# PowerNest.net
KiCad netlist of a schematic drawn in EAGLE
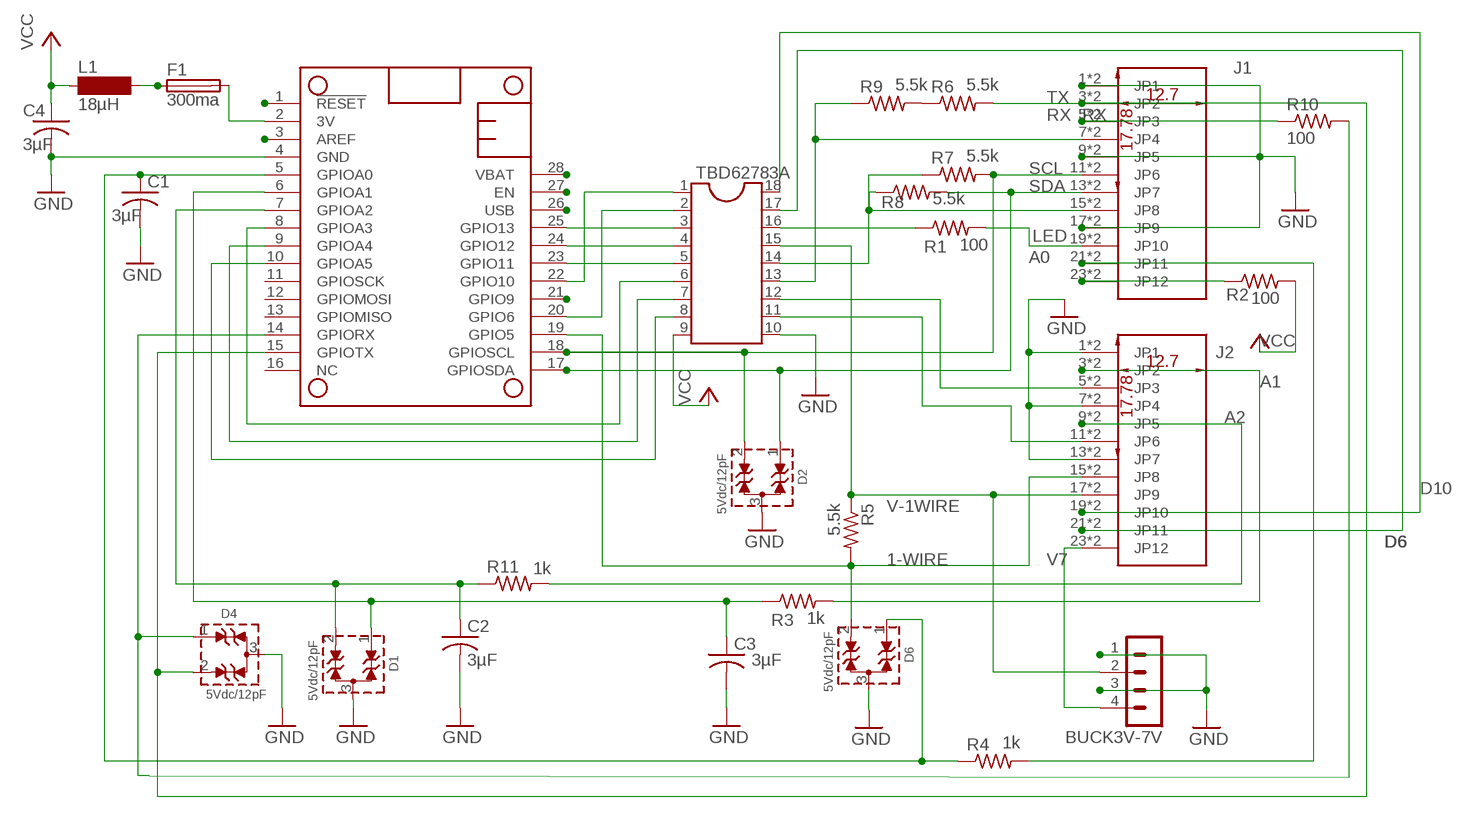
[diagram p0: schematic, sheet 1]

(export (version "E")
  (design (tool "Eeschema 10.0.6"))
  (components
    (comp (ref "BUCK3V-7V")
      (value "MA04-1")
      (footprint "eagle-import:MA04-1")
      (libsource (lib "eagle-import") (part "MA04-1"))
    )
    (comp (ref "C1")
      (value "3µF")
      (footprint "eagle-import:C1206K")
      (libsource (lib "eagle-import") (part "C-USC1206K"))
    )
    (comp (ref "C2")
      (value "3µF")
      (footprint "eagle-import:C1206K")
      (libsource (lib "eagle-import") (part "C-USC1206K"))
    )
    (comp (ref "C3")
      (value "3µF")
      (footprint "eagle-import:C1206K")
      (libsource (lib "eagle-import") (part "C-USC1206K"))
    )
    (comp (ref "C4")
      (value "3µF")
      (footprint "eagle-import:C1206K")
      (libsource (lib "eagle-import") (part "C-USC1206K"))
    )
    (comp (ref "D1")
      (value "5Vdc/12pF")
      (footprint "eagle-import:WE-TVS_SOT23-3L")
      (libsource (lib "eagle-import") (part "WE-TVS_SOT23-3L_824022"))
    )
    (comp (ref "D2")
      (value "5Vdc/12pF")
      (footprint "eagle-import:WE-TVS_SOT23-3L")
      (libsource (lib "eagle-import") (part "WE-TVS_SOT23-3L_824022"))
    )
    (comp (ref "D4")
      (value "5Vdc/12pF")
      (footprint "eagle-import:WE-TVS_SOT23-3L")
      (libsource (lib "eagle-import") (part "WE-TVS_SOT23-3L_824022"))
    )
    (comp (ref "D6")
      (value "5Vdc/12pF")
      (footprint "eagle-import:WE-TVS_SOT23-3L")
      (libsource (lib "eagle-import") (part "WE-TVS_SOT23-3L_824022"))
    )
    (comp (ref "F1")
      (value "300ma")
      (footprint "eagle-import:TE5")
      (libsource (lib "eagle-import") (part "TE5"))
    )
    (comp (ref "FEATHER")
      (value "FEATHERWING_NODIM")
      (footprint "eagle-import:FEATHERWING_DIM")
      (libsource (lib "eagle-import") (part "FEATHERWING_NODIM"))
    )
    (comp (ref "J1")
      (value "MC000008B")
      (footprint "eagle-import:CONNECTED")
      (libsource (lib "eagle-import") (part "MC000008B"))
    )
    (comp (ref "J2")
      (value "MC000008B")
      (footprint "eagle-import:CONNECTED")
      (libsource (lib "eagle-import") (part "MC000008B"))
    )
    (comp (ref "L1")
      (value "18µH")
      (footprint "eagle-import:BS11")
      (libsource (lib "eagle-import") (part "BS11"))
    )
    (comp (ref "R1")
      (value "100")
      (footprint "eagle-import:R1206")
      (libsource (lib "eagle-import") (part "R-US_R1206"))
    )
    (comp (ref "R2")
      (value "100")
      (footprint "eagle-import:R1206")
      (libsource (lib "eagle-import") (part "R-US_R1206"))
    )
    (comp (ref "R3")
      (value "1k")
      (footprint "eagle-import:R1206")
      (libsource (lib "eagle-import") (part "R-US_R1206"))
    )
    (comp (ref "R4")
      (value "1k")
      (footprint "eagle-import:R1206")
      (libsource (lib "eagle-import") (part "R-US_R1206"))
    )
    (comp (ref "R5")
      (value "5.5k")
      (footprint "eagle-import:R1206")
      (libsource (lib "eagle-import") (part "R-US_R1206"))
    )
    (comp (ref "R6")
      (value "5.5k")
      (footprint "eagle-import:R1206")
      (libsource (lib "eagle-import") (part "R-US_R1206"))
    )
    (comp (ref "R7")
      (value "5.5k")
      (footprint "eagle-import:R1206")
      (libsource (lib "eagle-import") (part "R-US_R1206"))
    )
    (comp (ref "R8")
      (value "5.5k")
      (footprint "eagle-import:R1206")
      (libsource (lib "eagle-import") (part "R-US_R1206"))
    )
    (comp (ref "R9")
      (value "5.5k")
      (footprint "eagle-import:R1206")
      (libsource (lib "eagle-import") (part "R-US_R1206"))
    )
    (comp (ref "R10")
      (value "100")
      (footprint "eagle-import:R1206")
      (libsource (lib "eagle-import") (part "R-US_R1206"))
    )
    (comp (ref "R11")
      (value "1k")
      (footprint "eagle-import:R1206")
      (libsource (lib "eagle-import") (part "R-US_R1206"))
    )
    (comp (ref "TBD62783A")
      (value "DIL18S")
      (footprint "eagle-import:SOCKET-18")
      (libsource (lib "eagle-import") (part "DIL18S"))
    )
  )
  (nets
    (net (code "1") (name "/1-WIRE") (class "Default")
      (node (ref "D6") (pin "2") (pinfunction "I/O2_2") (pintype "bidirectional"))
      (node (ref "FEATHER") (pin "19") (pinfunction "GPIO5_19") (pintype "bidirectional"))
      (node (ref "J2") (pin "15") (pinfunction "JP8_15") (pintype "bidirectional"))
      (node (ref "J2") (pin "16") (pinfunction "JP8_16") (pintype "bidirectional"))
      (node (ref "R5") (pin "2") (pinfunction "2_2") (pintype "passive"))
    )
    (net (code "2") (name "/A0") (class "Default")
      (node (ref "J1") (pin "21") (pinfunction "JP11_21") (pintype "bidirectional"))
      (node (ref "J1") (pin "22") (pinfunction "JP11_22") (pintype "bidirectional"))
      (node (ref "R4") (pin "2") (pinfunction "2_2") (pintype "passive"))
    )
    (net (code "3") (name "/A1") (class "Default")
      (node (ref "J2") (pin "3") (pinfunction "JP2_3") (pintype "bidirectional"))
      (node (ref "J2") (pin "4") (pinfunction "JP2_4") (pintype "bidirectional"))
      (node (ref "R3") (pin "2") (pinfunction "2_2") (pintype "passive"))
    )
    (net (code "4") (name "/A2") (class "Default")
      (node (ref "J2") (pin "10") (pinfunction "JP5_10") (pintype "bidirectional"))
      (node (ref "J2") (pin "9") (pinfunction "JP5_9") (pintype "bidirectional"))
      (node (ref "R11") (pin "2") (pinfunction "2_2") (pintype "passive"))
    )
    (net (code "5") (name "/D6") (class "Default")
      (node (ref "J2") (pin "21") (pinfunction "JP11_21") (pintype "bidirectional"))
      (node (ref "J2") (pin "22") (pinfunction "JP11_22") (pintype "bidirectional"))
      (node (ref "TBD62783A") (pin "17") (pinfunction "17_17") (pintype "passive"))
    )
    (net (code "6") (name "/D10") (class "Default")
      (node (ref "J2") (pin "19") (pinfunction "JP10_19") (pintype "bidirectional"))
      (node (ref "J2") (pin "20") (pinfunction "JP10_20") (pintype "bidirectional"))
      (node (ref "TBD62783A") (pin "18") (pinfunction "18_18") (pintype "passive"))
    )
    (net (code "7") (name "/LED") (class "Default")
      (node (ref "J1") (pin "19") (pinfunction "JP10_19") (pintype "bidirectional"))
      (node (ref "J1") (pin "20") (pinfunction "JP10_20") (pintype "bidirectional"))
      (node (ref "R1") (pin "2") (pinfunction "2_2") (pintype "passive"))
    )
    (net (code "8") (name "/RX") (class "Default")
      (node (ref "J1") (pin "5") (pinfunction "JP3_5") (pintype "bidirectional"))
      (node (ref "J1") (pin "6") (pinfunction "JP3_6") (pintype "bidirectional"))
      (node (ref "R10") (pin "1") (pinfunction "1_1") (pintype "passive"))
    )
    (net (code "9") (name "/SCL") (class "Default")
      (node (ref "D2") (pin "2") (pinfunction "I/O2_2") (pintype "bidirectional"))
      (node (ref "FEATHER") (pin "18") (pinfunction "GPIOSCL_18") (pintype "bidirectional"))
      (node (ref "J1") (pin "11") (pinfunction "JP6_11") (pintype "bidirectional"))
      (node (ref "J1") (pin "12") (pinfunction "JP6_12") (pintype "bidirectional"))
      (node (ref "R7") (pin "2") (pinfunction "2_2") (pintype "passive"))
    )
    (net (code "10") (name "/SDA") (class "Default")
      (node (ref "D2") (pin "1") (pinfunction "I/O1_1") (pintype "bidirectional"))
      (node (ref "FEATHER") (pin "17") (pinfunction "GPIOSDA_17") (pintype "bidirectional"))
      (node (ref "J1") (pin "13") (pinfunction "JP7_13") (pintype "bidirectional"))
      (node (ref "J1") (pin "14") (pinfunction "JP7_14") (pintype "bidirectional"))
      (node (ref "R8") (pin "2") (pinfunction "2_2") (pintype "passive"))
    )
    (net (code "11") (name "/TX") (class "Default")
      (node (ref "D4") (pin "2") (pinfunction "I/O2_2") (pintype "bidirectional"))
      (node (ref "FEATHER") (pin "15") (pinfunction "GPIOTX_15") (pintype "bidirectional"))
      (node (ref "J1") (pin "3") (pinfunction "JP2_3") (pintype "bidirectional"))
      (node (ref "J1") (pin "4") (pinfunction "JP2_4") (pintype "bidirectional"))
      (node (ref "R6") (pin "2") (pinfunction "2_2") (pintype "passive"))
    )
    (net (code "12") (name "/USB") (class "Default")
      (node (ref "FEATHER") (pin "26") (pinfunction "USB_26") (pintype "power_in"))
    )
    (net (code "13") (name "/V-1WIRE") (class "Default")
      (node (ref "BUCK3V-7V") (pin "2") (pinfunction "2_2") (pintype "passive"))
      (node (ref "J2") (pin "17") (pinfunction "JP9_17") (pintype "bidirectional"))
      (node (ref "J2") (pin "18") (pinfunction "JP9_18") (pintype "bidirectional"))
      (node (ref "R5") (pin "1") (pinfunction "1_1") (pintype "passive"))
      (node (ref "TBD62783A") (pin "15") (pinfunction "15_15") (pintype "passive"))
    )
    (net (code "14") (name "/V7") (class "Default")
      (node (ref "BUCK3V-7V") (pin "4") (pinfunction "4_4") (pintype "passive"))
      (node (ref "J2") (pin "23") (pinfunction "JP12_23") (pintype "bidirectional"))
      (node (ref "J2") (pin "24") (pinfunction "JP12_24") (pintype "bidirectional"))
    )
    (net (code "15") (name "/VBAT") (class "Default")
      (node (ref "FEATHER") (pin "28") (pinfunction "VBAT_28") (pintype "power_in"))
    )
    (net (code "16") (name "GND") (class "Default")
      (node (ref "BUCK3V-7V") (pin "1") (pinfunction "1_1") (pintype "passive"))
      (node (ref "BUCK3V-7V") (pin "3") (pinfunction "3_3") (pintype "passive"))
      (node (ref "C1") (pin "2") (pinfunction "2_2") (pintype "passive"))
      (node (ref "C2") (pin "2") (pinfunction "2_2") (pintype "passive"))
      (node (ref "C3") (pin "2") (pinfunction "2_2") (pintype "passive"))
      (node (ref "C4") (pin "2") (pinfunction "2_2") (pintype "passive"))
      (node (ref "D1") (pin "3") (pinfunction "GND_3") (pintype "power_in"))
      (node (ref "D2") (pin "3") (pinfunction "GND_3") (pintype "power_in"))
      (node (ref "D4") (pin "3") (pinfunction "GND_3") (pintype "power_in"))
      (node (ref "D6") (pin "3") (pinfunction "GND_3") (pintype "power_in"))
      (node (ref "FEATHER") (pin "4") (pinfunction "GND_4") (pintype "power_in"))
      (node (ref "J1") (pin "1") (pinfunction "JP1_1") (pintype "bidirectional"))
      (node (ref "J1") (pin "10") (pinfunction "JP5_10") (pintype "bidirectional"))
      (node (ref "J1") (pin "17") (pinfunction "JP9_17") (pintype "bidirectional"))
      (node (ref "J1") (pin "18") (pinfunction "JP9_18") (pintype "bidirectional"))
      (node (ref "J1") (pin "2") (pinfunction "JP1_2") (pintype "bidirectional"))
      (node (ref "J1") (pin "9") (pinfunction "JP5_9") (pintype "bidirectional"))
      (node (ref "J2") (pin "1") (pinfunction "JP1_1") (pintype "bidirectional"))
      (node (ref "J2") (pin "13") (pinfunction "JP7_13") (pintype "bidirectional"))
      (node (ref "J2") (pin "14") (pinfunction "JP7_14") (pintype "bidirectional"))
      (node (ref "J2") (pin "2") (pinfunction "JP1_2") (pintype "bidirectional"))
      (node (ref "J2") (pin "7") (pinfunction "JP4_7") (pintype "bidirectional"))
      (node (ref "J2") (pin "8") (pinfunction "JP4_8") (pintype "bidirectional"))
      (node (ref "TBD62783A") (pin "10") (pinfunction "10_10") (pintype "passive"))
    )
    (net (code "17") (name "Net-(D1-I{slash}O1)") (class "Default")
      (node (ref "C3") (pin "1") (pinfunction "1_1") (pintype "passive"))
      (node (ref "D1") (pin "1") (pinfunction "I/O1_1") (pintype "bidirectional"))
      (node (ref "FEATHER") (pin "6") (pinfunction "GPIOA1_6") (pintype "bidirectional"))
      (node (ref "R3") (pin "1") (pinfunction "1_1") (pintype "passive"))
    )
    (net (code "18") (name "Net-(D1-I{slash}O2)") (class "Default")
      (node (ref "C2") (pin "1") (pinfunction "1_1") (pintype "passive"))
      (node (ref "D1") (pin "2") (pinfunction "I/O2_2") (pintype "bidirectional"))
      (node (ref "FEATHER") (pin "7") (pinfunction "GPIOA2_7") (pintype "bidirectional"))
      (node (ref "R11") (pin "1") (pinfunction "1_1") (pintype "passive"))
    )
    (net (code "19") (name "Net-(D4-I{slash}O1)") (class "Default")
      (node (ref "D4") (pin "1") (pinfunction "I/O1_1") (pintype "bidirectional"))
      (node (ref "FEATHER") (pin "14") (pinfunction "GPIORX_14") (pintype "bidirectional"))
      (node (ref "R10") (pin "2") (pinfunction "2_2") (pintype "passive"))
    )
    (net (code "20") (name "Net-(D6-I{slash}O1)") (class "Default")
      (node (ref "C1") (pin "1") (pinfunction "1_1") (pintype "passive"))
      (node (ref "D6") (pin "1") (pinfunction "I/O1_1") (pintype "bidirectional"))
      (node (ref "FEATHER") (pin "5") (pinfunction "GPIOA0_5") (pintype "bidirectional"))
      (node (ref "R4") (pin "1") (pinfunction "1_1") (pintype "passive"))
    )
    (net (code "21") (name "Net-(F1-Pad1)") (class "Default")
      (node (ref "F1") (pin "1") (pinfunction "1_1") (pintype "passive"))
      (node (ref "L1") (pin "2") (pinfunction "2_2") (pintype "passive"))
    )
    (net (code "22") (name "Net-(FEATHER-3V)") (class "Default")
      (node (ref "F1") (pin "2") (pinfunction "2_2") (pintype "passive"))
      (node (ref "FEATHER") (pin "2") (pinfunction "3V_2") (pintype "power_in"))
    )
    (net (code "23") (name "Net-(FEATHER-GPIO6)") (class "Default")
      (node (ref "FEATHER") (pin "20") (pinfunction "GPIO6_20") (pintype "bidirectional"))
      (node (ref "TBD62783A") (pin "2") (pinfunction "2_2") (pintype "passive"))
    )
    (net (code "24") (name "Net-(FEATHER-GPIO10)") (class "Default")
      (node (ref "FEATHER") (pin "22") (pinfunction "GPIO10_22") (pintype "bidirectional"))
      (node (ref "TBD62783A") (pin "1") (pinfunction "1_1") (pintype "passive"))
    )
    (net (code "25") (name "Net-(FEATHER-GPIO11)") (class "Default")
      (node (ref "FEATHER") (pin "23") (pinfunction "GPIO11_23") (pintype "bidirectional"))
      (node (ref "TBD62783A") (pin "5") (pinfunction "5_5") (pintype "passive"))
    )
    (net (code "26") (name "Net-(FEATHER-GPIO12)") (class "Default")
      (node (ref "FEATHER") (pin "24") (pinfunction "GPIO12_24") (pintype "bidirectional"))
      (node (ref "TBD62783A") (pin "4") (pinfunction "4_4") (pintype "passive"))
    )
    (net (code "27") (name "Net-(FEATHER-GPIO13)") (class "Default")
      (node (ref "FEATHER") (pin "25") (pinfunction "GPIO13_25") (pintype "bidirectional"))
      (node (ref "TBD62783A") (pin "3") (pinfunction "3_3") (pintype "passive"))
    )
    (net (code "28") (name "Net-(FEATHER-GPIOA3)") (class "Default")
      (node (ref "FEATHER") (pin "8") (pinfunction "GPIOA3_8") (pintype "bidirectional"))
      (node (ref "TBD62783A") (pin "6") (pinfunction "6_6") (pintype "passive"))
    )
    (net (code "29") (name "Net-(FEATHER-GPIOA4)") (class "Default")
      (node (ref "FEATHER") (pin "9") (pinfunction "GPIOA4_9") (pintype "bidirectional"))
      (node (ref "TBD62783A") (pin "7") (pinfunction "7_7") (pintype "passive"))
    )
    (net (code "30") (name "Net-(FEATHER-GPIOA5)") (class "Default")
      (node (ref "FEATHER") (pin "10") (pinfunction "GPIOA5_10") (pintype "bidirectional"))
      (node (ref "TBD62783A") (pin "8") (pinfunction "8_8") (pintype "passive"))
    )
    (net (code "31") (name "Net-(J1-JP4-Pad7)") (class "Default")
      (node (ref "J1") (pin "7") (pinfunction "JP4_7") (pintype "bidirectional"))
      (node (ref "J1") (pin "8") (pinfunction "JP4_8") (pintype "bidirectional"))
      (node (ref "R9") (pin "1") (pinfunction "1_1") (pintype "passive"))
      (node (ref "TBD62783A") (pin "13") (pinfunction "13_13") (pintype "passive"))
    )
    (net (code "32") (name "Net-(J1-JP8-Pad15)") (class "Default")
      (node (ref "J1") (pin "15") (pinfunction "JP8_15") (pintype "bidirectional"))
      (node (ref "J1") (pin "16") (pinfunction "JP8_16") (pintype "bidirectional"))
      (node (ref "R7") (pin "1") (pinfunction "1_1") (pintype "passive"))
      (node (ref "R8") (pin "1") (pinfunction "1_1") (pintype "passive"))
      (node (ref "TBD62783A") (pin "14") (pinfunction "14_14") (pintype "passive"))
    )
    (net (code "33") (name "Net-(J1-JP12-Pad23)") (class "Default")
      (node (ref "J1") (pin "23") (pinfunction "JP12_23") (pintype "bidirectional"))
      (node (ref "J1") (pin "24") (pinfunction "JP12_24") (pintype "bidirectional"))
      (node (ref "R2") (pin "1") (pinfunction "1_1") (pintype "passive"))
    )
    (net (code "34") (name "Net-(J2-JP3-Pad5)") (class "Default")
      (node (ref "J2") (pin "5") (pinfunction "JP3_5") (pintype "bidirectional"))
      (node (ref "J2") (pin "6") (pinfunction "JP3_6") (pintype "bidirectional"))
      (node (ref "TBD62783A") (pin "12") (pinfunction "12_12") (pintype "passive"))
    )
    (net (code "35") (name "Net-(J2-JP6-Pad11)") (class "Default")
      (node (ref "J2") (pin "11") (pinfunction "JP6_11") (pintype "bidirectional"))
      (node (ref "J2") (pin "12") (pinfunction "JP6_12") (pintype "bidirectional"))
      (node (ref "TBD62783A") (pin "11") (pinfunction "11_11") (pintype "passive"))
    )
    (net (code "36") (name "Net-(R1-Pad1)") (class "Default")
      (node (ref "R1") (pin "1") (pinfunction "1_1") (pintype "passive"))
      (node (ref "TBD62783A") (pin "16") (pinfunction "16_16") (pintype "passive"))
    )
    (net (code "37") (name "Net-(R6-Pad1)") (class "Default")
      (node (ref "R6") (pin "1") (pinfunction "1_1") (pintype "passive"))
      (node (ref "R9") (pin "2") (pinfunction "2_2") (pintype "passive"))
    )
    (net (code "38") (name "VCC") (class "Default")
      (node (ref "C4") (pin "1") (pinfunction "1_1") (pintype "passive"))
      (node (ref "L1") (pin "1") (pinfunction "1_1") (pintype "passive"))
      (node (ref "R2") (pin "2") (pinfunction "2_2") (pintype "passive"))
      (node (ref "TBD62783A") (pin "9") (pinfunction "9_9") (pintype "passive"))
    )
    (net (code "39") (name "unconnected-(FEATHER-AREF-Pad3)") (class "Default")
      (node (ref "FEATHER") (pin "3") (pinfunction "AREF_3") (pintype "passive"))
    )
    (net (code "40") (name "unconnected-(FEATHER-EN-Pad27)") (class "Default")
      (node (ref "FEATHER") (pin "27") (pinfunction "EN_27") (pintype "passive"))
    )
    (net (code "41") (name "unconnected-(FEATHER-GPIO9-Pad21)") (class "Default")
      (node (ref "FEATHER") (pin "21") (pinfunction "GPIO9_21") (pintype "bidirectional"))
    )
    (net (code "42") (name "unconnected-(FEATHER-GPIOMISO-Pad13)") (class "Default")
      (node (ref "FEATHER") (pin "13") (pinfunction "GPIOMISO_13") (pintype "bidirectional"))
    )
    (net (code "43") (name "unconnected-(FEATHER-GPIOMOSI-Pad12)") (class "Default")
      (node (ref "FEATHER") (pin "12") (pinfunction "GPIOMOSI_12") (pintype "bidirectional"))
    )
    (net (code "44") (name "unconnected-(FEATHER-GPIOSCK-Pad11)") (class "Default")
      (node (ref "FEATHER") (pin "11") (pinfunction "GPIOSCK_11") (pintype "bidirectional"))
    )
    (net (code "45") (name "unconnected-(FEATHER-NC-Pad16)") (class "Default")
      (node (ref "FEATHER") (pin "16") (pinfunction "NC_16") (pintype "passive"))
    )
    (net (code "46") (name "unconnected-(FEATHER-~{RESET}-Pad1)") (class "Default")
      (node (ref "FEATHER") (pin "1") (pinfunction "~{RESET}_1") (pintype "input"))
    )
  )
)
